# Flasher.net
KiCad netlist of a schematic drawn in Altium Designer
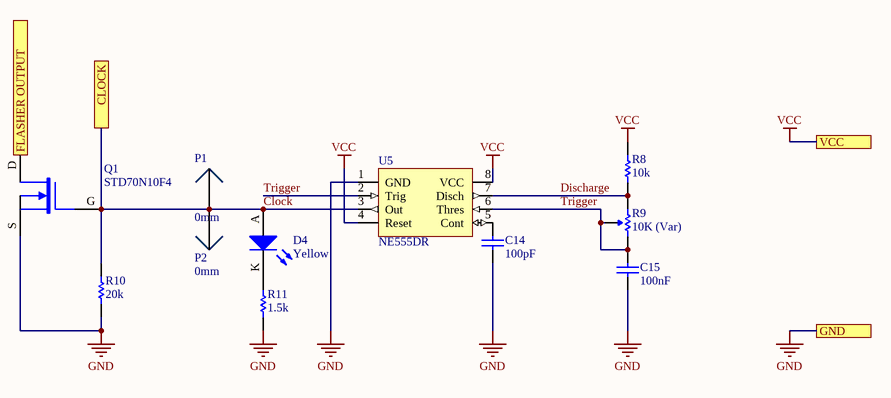
[diagram p0: Flasher.SchDoc]

(export (version "E")
  (design (tool "Eeschema 10.0.6"))
  (components
    (comp (ref "C14")
      (value "100pF")
      (footprint "0805")
      (fields
        (field (name "PART NUMBER") "GCM21B5C1H101JA37L")
        (field (name "TOLERANCE") "5%")
        (field (name "MANUFACTURER") "muRata")
      )
      (libsource (lib "ts_20-standard-library") (part "Capacitor"))
    )
    (comp (ref "C15")
      (value "100nF")
      (footprint "0805")
      (fields
        (field (name "PART NUMBER") "GCM21BR71E104KA37L")
        (field (name "TOLERANCE") "10%")
        (field (name "MANUFACTURER") "muRata")
      )
      (libsource (lib "ts_20-standard-library") (part "Capacitor"))
    )
    (comp (ref "D4")
      (value "Yellow")
      (footprint "0805 LED")
      (description "Yellow LED Indication - Discrete 1.75V 0805 (2012 Metric)")
      (fields (field (name "PART NUMBER") "SML-211YTT86") (field (name "MANUFACTURER") "ROHM Semiconductor"))
      (libsource (lib "ts_20-standard-library") (part "LED"))
    )
    (comp (ref "P1")
      (value "0mm")
      (footprint "SMD Test Point")
      (fields (field (name "PART NUMBER") "SMD Test Point") (field (name "CONTACT") "NA"))
      (libsource (lib "ts_20-standard-connectors") (part "Test Point"))
    )
    (comp (ref "P2")
      (value "0mm")
      (footprint "TH Test Point")
      (fields (field (name "PART NUMBER") "TH Test Point") (field (name "CONTACT") "NA"))
      (libsource (lib "ts_20-standard-connectors") (part "Test Point"))
    )
    (comp (ref "Q1")
      (value "STD70N10F4")
      (footprint "STM TO-252 MOSFET")
      (description "N-Channel 100V 60A (Tc) 125W (Tc) Surface Mount DPAK")
      (fields
        (field (name "MANUFACTURER") "STMicroelectronics")
        (field (name "DIGIKEY PART NUMBER") "497-8806-2-ND")
        (field (name "PUBLISHER") "Altium Limited")
      )
      (libsource (lib "ts_20-standard-library") (part "MOSFET-N"))
    )
    (comp (ref "R8")
      (value "10k")
      (footprint "0805")
      (fields
        (field (name "PART NUMBER") "RC0805FR0710KL")
        (field (name "MANUFACTURER") "YAGEO")
        (field (name "TOLERANCE") "0.01")
      )
      (libsource (lib "ts_20-standard-library") (part "Resistor"))
    )
    (comp (ref "R9")
      (value "10K (Var)")
      (footprint "B 3296")
      (fields
        (field (name "PART NUMBER") "3296W-1-103LF")
        (field (name "MANUFACTURER") "Bournes Inc")
        (field (name "TOLERANCE") "0.1")
      )
      (libsource (lib "ts_20-standard-library") (part "Resistor (Potentiometer)"))
    )
    (comp (ref "R10")
      (value "20k")
      (footprint "0805")
      (fields
        (field (name "PART NUMBER") "RC0805FR0720KL")
        (field (name "MANUFACTURER") "YAGEO")
        (field (name "TOLERANCE") "0.01")
      )
      (libsource (lib "ts_20-standard-library") (part "Resistor"))
    )
    (comp (ref "R11")
      (value "1.5k")
      (footprint "0805")
      (fields
        (field (name "PART NUMBER") "RC0805FR071K5L")
        (field (name "MANUFACTURER") "YAGEO")
        (field (name "TOLERANCE") "0.01")
      )
      (libsource (lib "ts_20-standard-library") (part "Resistor"))
    )
    (comp (ref "U5")
      (value "NE555DR")
      (footprint "TI 8-SOIC")
      (description "IC OSC SGL TIMER 100KHZ 8-SOIC")
      (fields
        (field (name "MANUFACTURER") "Texas Instruments")
        (field (name "DIGIKEY PART NUMBER") "296-6501-1-ND")
      )
      (libsource (lib "ts_20-standard-library") (part "NE555DR"))
    )
  )
  (nets
    (net (code "1") (name "/Clock") (class "Default")
      (node (ref "D4") (pin "A") (pinfunction "A_A") (pintype "passive"))
      (node (ref "P1") (pin "1") (pinfunction "1_1") (pintype "passive"))
      (node (ref "P2") (pin "1") (pinfunction "1_1") (pintype "passive"))
      (node (ref "Q1") (pin "G") (pinfunction "G_G") (pintype "passive"))
      (node (ref "R10") (pin "2") (pinfunction "2_2") (pintype "passive"))
      (node (ref "U5") (pin "3") (pinfunction "Out_3") (pintype "output"))
    )
    (net (code "2") (name "/Discharge") (class "Default")
      (node (ref "R8") (pin "1") (pinfunction "1_1") (pintype "passive"))
      (node (ref "R9") (pin "3") (pinfunction "CW_3") (pintype "passive"))
      (node (ref "U5") (pin "7") (pinfunction "Disch_7") (pintype "output"))
    )
    (net (code "3") (name "/FLASHER OUTPUT") (class "Default")
      (node (ref "Q1") (pin "D") (pinfunction "D_D") (pintype "passive"))
    )
    (net (code "4") (name "/Trigger") (class "Default")
      (node (ref "C15") (pin "2") (pinfunction "2_2") (pintype "passive"))
      (node (ref "R9") (pin "1") (pinfunction "CCW_1") (pintype "passive"))
      (node (ref "R9") (pin "2") (pinfunction "Wiper_2") (pintype "passive"))
      (node (ref "U5") (pin "2") (pinfunction "Trig_2") (pintype "input"))
      (node (ref "U5") (pin "6") (pinfunction "Thres_6") (pintype "input"))
    )
    (net (code "5") (name "GND") (class "Default")
      (node (ref "C14") (pin "1") (pinfunction "1_1") (pintype "passive"))
      (node (ref "C15") (pin "1") (pinfunction "1_1") (pintype "passive"))
      (node (ref "Q1") (pin "S") (pinfunction "S_S") (pintype "passive"))
      (node (ref "R10") (pin "1") (pinfunction "1_1") (pintype "passive"))
      (node (ref "R11") (pin "1") (pinfunction "1_1") (pintype "passive"))
      (node (ref "U5") (pin "1") (pinfunction "GND_1") (pintype "power_in"))
    )
    (net (code "6") (name "Net-(D4-PadK)") (class "Default")
      (node (ref "D4") (pin "K") (pinfunction "K_K") (pintype "passive"))
      (node (ref "R11") (pin "2") (pinfunction "2_2") (pintype "passive"))
    )
    (net (code "7") (name "Net-(U5-Cont)") (class "Default")
      (node (ref "C14") (pin "2") (pinfunction "2_2") (pintype "passive"))
      (node (ref "U5") (pin "5") (pinfunction "Cont_5") (pintype "bidirectional"))
    )
    (net (code "8") (name "VCC") (class "Default")
      (node (ref "R8") (pin "2") (pinfunction "2_2") (pintype "passive"))
      (node (ref "U5") (pin "4") (pinfunction "Reset_4") (pintype "passive"))
      (node (ref "U5") (pin "8") (pinfunction "VCC_8") (pintype "passive"))
    )
  )
)
